# 2Wireless.net
KiCad netlist of a schematic drawn in EAGLE
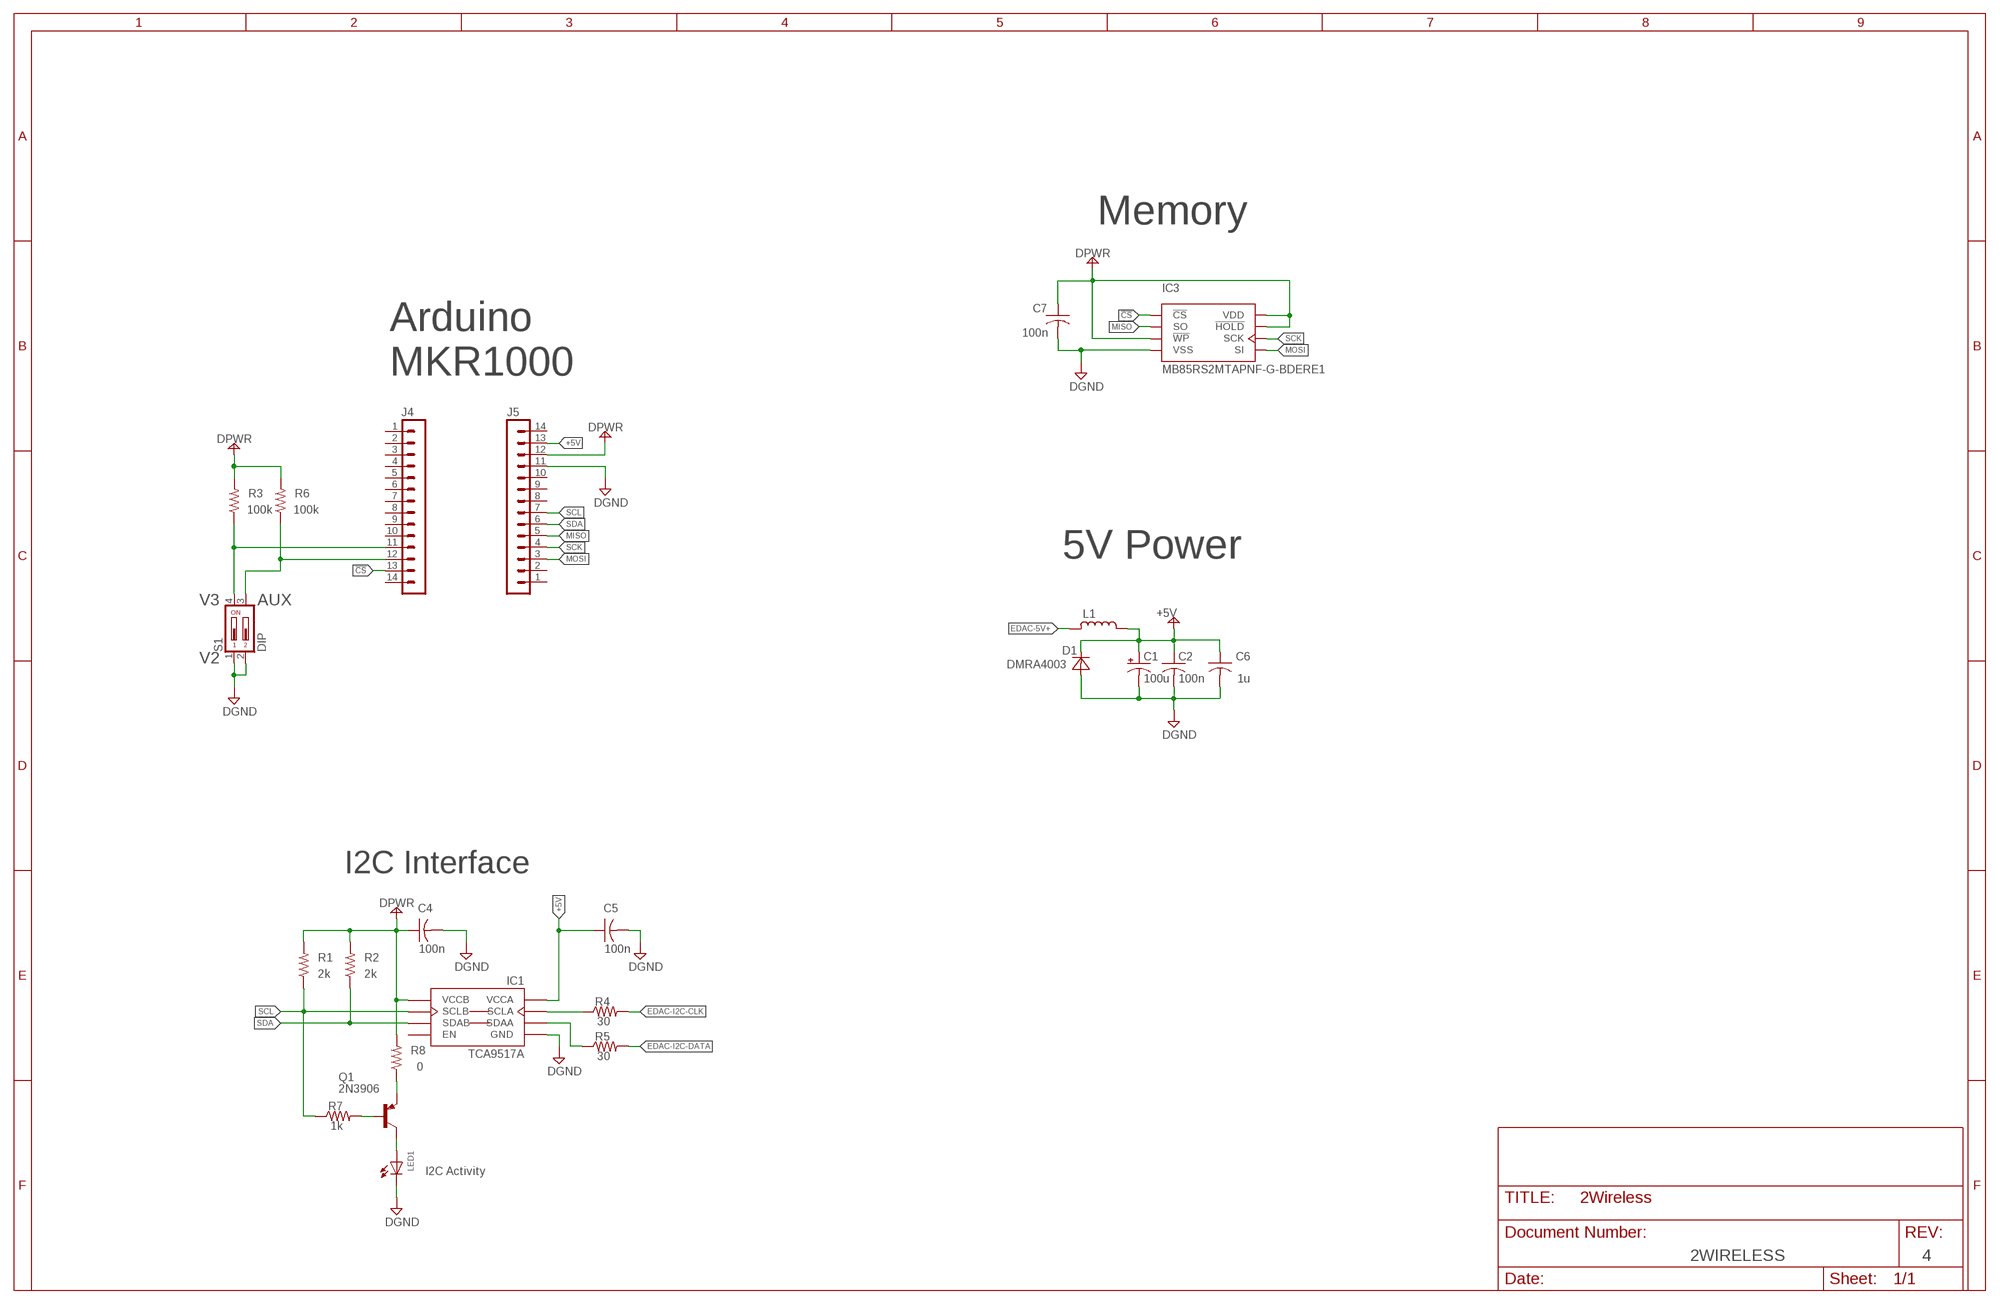
[diagram p0: schematic, sheet 1]

(export (version "E")
  (design (tool "Eeschema 10.0.6"))
  (components
    (comp (ref "C1")
      (value "100u")
      (footprint "eagle-import:PAN-D")
      (fields (field (name "MF") "PANASONIC") (field (name "MPN") "EEE-1CA101WP"))
      (libsource (lib "eagle-import") (part "C-POLPD"))
    )
    (comp (ref "C2")
      (value "100n")
      (footprint "eagle-import:C0603")
      (libsource (lib "eagle-import") (part "CB"))
    )
    (comp (ref "C4")
      (value "100n")
      (footprint "eagle-import:C0603")
      (libsource (lib "eagle-import") (part "CB"))
    )
    (comp (ref "C5")
      (value "100n")
      (footprint "eagle-import:C0603")
      (libsource (lib "eagle-import") (part "CB"))
    )
    (comp (ref "C6")
      (value "1u")
      (footprint "eagle-import:C0603")
      (libsource (lib "eagle-import") (part "CB"))
    )
    (comp (ref "C7")
      (value "100n")
      (footprint "eagle-import:C0603")
      (libsource (lib "eagle-import") (part "CB"))
    )
    (comp (ref "D1")
      (value "DMRA4003")
      (footprint "eagle-import:SMA")
      (fields (field (name "MF") "ON") (field (name "MPN") "MRA4003T3G"))
      (libsource (lib "eagle-import") (part "DMRA4003"))
    )
    (comp (ref "IC1")
      (value "TCA9517A")
      (footprint "eagle-import:MSOP8")
      (fields (field (name "MF") "TI") (field (name "MPN") "TCA9517ADGKR"))
      (libsource (lib "eagle-import") (part "I2C-ISOLATORTCA9517A"))
    )
    (comp (ref "IC3")
      (value "MB85RS2MTAPNF-G-BDERE1")
      (footprint "eagle-import:SO08")
      (fields (field (name "MF") "FUJITSU"))
      (libsource (lib "eagle-import") (part "FRAMSPI"))
    )
    (comp (ref "J4")
      (value "MA14-1")
      (footprint "eagle-import:MA14-1")
      (libsource (lib "eagle-import") (part "MA14-1"))
    )
    (comp (ref "J5")
      (value "MA14-1")
      (footprint "eagle-import:MA14-1")
      (libsource (lib "eagle-import") (part "MA14-1"))
    )
    (comp (ref "L1")
      (value "LB")
      (footprint "eagle-import:0603")
      (fields (field (name "MF") "WURTH") (field (name "MPN") "742792609"))
      (libsource (lib "eagle-import") (part "LB"))
    )
    (comp (ref "LED1")
      (value "LED0805BLUE")
      (footprint "eagle-import:CHIPLED_0805")
      (libsource (lib "eagle-import") (part "LED0805BLUE"))
    )
    (comp (ref "Q1")
      (value "2N3906")
      (footprint "eagle-import:SOT23")
      (fields (field (name "MF") "FAIRCHILD") (field (name "MPN") "MMBT3906"))
      (libsource (lib "eagle-import") (part "PNPMMBT3906"))
    )
    (comp (ref "R1")
      (value "2k")
      (footprint "eagle-import:R0603")
      (libsource (lib "eagle-import") (part "RB"))
    )
    (comp (ref "R2")
      (value "2k")
      (footprint "eagle-import:R0603")
      (libsource (lib "eagle-import") (part "RB"))
    )
    (comp (ref "R3")
      (value "100k")
      (footprint "eagle-import:R0603")
      (libsource (lib "eagle-import") (part "RB"))
    )
    (comp (ref "R4")
      (value "30")
      (footprint "eagle-import:R0603")
      (libsource (lib "eagle-import") (part "RB"))
    )
    (comp (ref "R5")
      (value "30")
      (footprint "eagle-import:R0603")
      (libsource (lib "eagle-import") (part "RB"))
    )
    (comp (ref "R6")
      (value "100k")
      (footprint "eagle-import:R0603")
      (libsource (lib "eagle-import") (part "RB"))
    )
    (comp (ref "R7")
      (value "1k")
      (footprint "eagle-import:R0603")
      (libsource (lib "eagle-import") (part "RB"))
    )
    (comp (ref "R8")
      (value "0")
      (footprint "eagle-import:R0603")
      (libsource (lib "eagle-import") (part "RB"))
    )
    (comp (ref "S1")
      (value "DIP")
      (footprint "eagle-import:CTS-219-02")
      (fields (field (name "MF") "CTS") (field (name "MPN") "219-2MST"))
      (libsource (lib "eagle-import") (part "219-02"))
    )
  )
  (nets
    (net (code "1") (name "+5V") (class "Default")
      (node (ref "C1") (pin "+") (pinfunction "+_+") (pintype "passive"))
      (node (ref "C2") (pin "1") (pinfunction "1_1") (pintype "passive"))
      (node (ref "C5") (pin "1") (pinfunction "1_1") (pintype "passive"))
      (node (ref "C6") (pin "1") (pinfunction "1_1") (pintype "passive"))
      (node (ref "D1") (pin "K") (pinfunction "C_K") (pintype "passive"))
      (node (ref "IC1") (pin "1") (pinfunction "VCCA_1") (pintype "power_in"))
      (node (ref "J5") (pin "13") (pinfunction "13_13") (pintype "passive"))
      (node (ref "L1") (pin "2") (pinfunction "4_2") (pintype "passive"))
    )
    (net (code "2") (name "/~{CS}") (class "Default")
      (node (ref "IC3") (pin "1") (pinfunction "~{CS}_1") (pintype "input"))
      (node (ref "J4") (pin "13") (pinfunction "13_13") (pintype "passive"))
    )
    (net (code "3") (name "DGND") (class "Default")
      (node (ref "C1") (pin "-") (pinfunction "-_-") (pintype "passive"))
      (node (ref "C2") (pin "2") (pinfunction "2_2") (pintype "passive"))
      (node (ref "C4") (pin "2") (pinfunction "2_2") (pintype "passive"))
      (node (ref "C5") (pin "2") (pinfunction "2_2") (pintype "passive"))
      (node (ref "C6") (pin "2") (pinfunction "2_2") (pintype "passive"))
      (node (ref "C7") (pin "2") (pinfunction "2_2") (pintype "passive"))
      (node (ref "D1") (pin "A") (pinfunction "A_A") (pintype "passive"))
      (node (ref "IC1") (pin "4") (pinfunction "GND_4") (pintype "power_in"))
      (node (ref "IC3") (pin "4") (pinfunction "VSS_4") (pintype "power_in"))
      (node (ref "J5") (pin "11") (pinfunction "11_11") (pintype "passive"))
      (node (ref "LED1") (pin "C") (pinfunction "C_C") (pintype "passive"))
      (node (ref "S1") (pin "1") (pinfunction "1_1") (pintype "passive"))
      (node (ref "S1") (pin "2") (pinfunction "2_2") (pintype "passive"))
    )
    (net (code "4") (name "DPWR") (class "Default")
      (node (ref "C4") (pin "1") (pinfunction "1_1") (pintype "passive"))
      (node (ref "C7") (pin "1") (pinfunction "1_1") (pintype "passive"))
      (node (ref "IC1") (pin "8") (pinfunction "VCCB_8") (pintype "power_in"))
      (node (ref "IC3") (pin "3") (pinfunction "~{WP}_3") (pintype "bidirectional"))
      (node (ref "IC3") (pin "7") (pinfunction "~{HOLD}_7") (pintype "bidirectional"))
      (node (ref "IC3") (pin "8") (pinfunction "VDD_8") (pintype "power_in"))
      (node (ref "J5") (pin "12") (pinfunction "12_12") (pintype "passive"))
      (node (ref "R1") (pin "2") (pinfunction "2_2") (pintype "passive"))
      (node (ref "R2") (pin "2") (pinfunction "2_2") (pintype "passive"))
      (node (ref "R3") (pin "2") (pinfunction "2_2") (pintype "passive"))
      (node (ref "R6") (pin "2") (pinfunction "2_2") (pintype "passive"))
      (node (ref "R8") (pin "2") (pinfunction "2_2") (pintype "passive"))
    )
    (net (code "5") (name "EDAC-5V+") (class "Default")
      (node (ref "L1") (pin "1") (pinfunction "1_1") (pintype "passive"))
    )
    (net (code "6") (name "EDAC-I2C-CLK") (class "Default")
      (node (ref "R4") (pin "2") (pinfunction "2_2") (pintype "passive"))
    )
    (net (code "7") (name "EDAC-I2C-DATA") (class "Default")
      (node (ref "R5") (pin "2") (pinfunction "2_2") (pintype "passive"))
    )
    (net (code "8") (name "MISO") (class "Default")
      (node (ref "IC3") (pin "2") (pinfunction "SO_2") (pintype "bidirectional"))
      (node (ref "J5") (pin "5") (pinfunction "5_5") (pintype "passive"))
    )
    (net (code "9") (name "MOSI") (class "Default")
      (node (ref "IC3") (pin "5") (pinfunction "SI_5") (pintype "bidirectional"))
      (node (ref "J5") (pin "3") (pinfunction "3_3") (pintype "passive"))
    )
    (net (code "10") (name "Net-(IC1-SCLA)") (class "Default")
      (node (ref "IC1") (pin "2") (pinfunction "SCLA_2") (pintype "bidirectional"))
      (node (ref "R4") (pin "1") (pinfunction "1_1") (pintype "passive"))
    )
    (net (code "11") (name "Net-(IC1-SDAA)") (class "Default")
      (node (ref "IC1") (pin "3") (pinfunction "SDAA_3") (pintype "bidirectional"))
      (node (ref "R5") (pin "1") (pinfunction "1_1") (pintype "passive"))
    )
    (net (code "12") (name "Net-(J4-Pad11)") (class "Default")
      (node (ref "J4") (pin "11") (pinfunction "11_11") (pintype "passive"))
      (node (ref "R3") (pin "1") (pinfunction "1_1") (pintype "passive"))
      (node (ref "S1") (pin "4") (pinfunction "4_4") (pintype "passive"))
    )
    (net (code "13") (name "Net-(J4-Pad12)") (class "Default")
      (node (ref "J4") (pin "12") (pinfunction "12_12") (pintype "passive"))
      (node (ref "R6") (pin "1") (pinfunction "1_1") (pintype "passive"))
      (node (ref "S1") (pin "3") (pinfunction "3_3") (pintype "passive"))
    )
    (net (code "14") (name "Net-(Q1-B)") (class "Default")
      (node (ref "Q1") (pin "1") (pinfunction "B_1") (pintype "passive"))
      (node (ref "R7") (pin "2") (pinfunction "2_2") (pintype "passive"))
    )
    (net (code "15") (name "Net-(Q1-C)") (class "Default")
      (node (ref "LED1") (pin "A") (pinfunction "A_A") (pintype "passive"))
      (node (ref "Q1") (pin "2") (pinfunction "C_2") (pintype "passive"))
    )
    (net (code "16") (name "Net-(Q1-E)") (class "Default")
      (node (ref "Q1") (pin "3") (pinfunction "E_3") (pintype "passive"))
      (node (ref "R8") (pin "1") (pinfunction "1_1") (pintype "passive"))
    )
    (net (code "17") (name "SCK") (class "Default")
      (node (ref "IC3") (pin "6") (pinfunction "SCK_6") (pintype "bidirectional"))
      (node (ref "J5") (pin "4") (pinfunction "4_4") (pintype "passive"))
    )
    (net (code "18") (name "SCL") (class "Default")
      (node (ref "IC1") (pin "7") (pinfunction "SCLB_7") (pintype "bidirectional"))
      (node (ref "J5") (pin "7") (pinfunction "7_7") (pintype "passive"))
      (node (ref "R1") (pin "1") (pinfunction "1_1") (pintype "passive"))
      (node (ref "R7") (pin "1") (pinfunction "1_1") (pintype "passive"))
    )
    (net (code "19") (name "SDA") (class "Default")
      (node (ref "IC1") (pin "6") (pinfunction "SDAB_6") (pintype "bidirectional"))
      (node (ref "J5") (pin "6") (pinfunction "6_6") (pintype "passive"))
      (node (ref "R2") (pin "1") (pinfunction "1_1") (pintype "passive"))
    )
    (net (code "20") (name "unconnected-(IC1-EN-Pad5)") (class "Default")
      (node (ref "IC1") (pin "5") (pinfunction "EN_5") (pintype "input"))
    )
    (net (code "21") (name "unconnected-(J4-Pad1)") (class "Default")
      (node (ref "J4") (pin "1") (pinfunction "1_1") (pintype "passive"))
    )
    (net (code "22") (name "unconnected-(J4-Pad2)") (class "Default")
      (node (ref "J4") (pin "2") (pinfunction "2_2") (pintype "passive"))
    )
    (net (code "23") (name "unconnected-(J4-Pad3)") (class "Default")
      (node (ref "J4") (pin "3") (pinfunction "3_3") (pintype "passive"))
    )
    (net (code "24") (name "unconnected-(J4-Pad4)") (class "Default")
      (node (ref "J4") (pin "4") (pinfunction "4_4") (pintype "passive"))
    )
    (net (code "25") (name "unconnected-(J4-Pad5)") (class "Default")
      (node (ref "J4") (pin "5") (pinfunction "5_5") (pintype "passive"))
    )
    (net (code "26") (name "unconnected-(J4-Pad6)") (class "Default")
      (node (ref "J4") (pin "6") (pinfunction "6_6") (pintype "passive"))
    )
    (net (code "27") (name "unconnected-(J4-Pad7)") (class "Default")
      (node (ref "J4") (pin "7") (pinfunction "7_7") (pintype "passive"))
    )
    (net (code "28") (name "unconnected-(J4-Pad8)") (class "Default")
      (node (ref "J4") (pin "8") (pinfunction "8_8") (pintype "passive"))
    )
    (net (code "29") (name "unconnected-(J4-Pad9)") (class "Default")
      (node (ref "J4") (pin "9") (pinfunction "9_9") (pintype "passive"))
    )
    (net (code "30") (name "unconnected-(J4-Pad10)") (class "Default")
      (node (ref "J4") (pin "10") (pinfunction "10_10") (pintype "passive"))
    )
    (net (code "31") (name "unconnected-(J4-Pad14)") (class "Default")
      (node (ref "J4") (pin "14") (pinfunction "14_14") (pintype "passive"))
    )
    (net (code "32") (name "unconnected-(J5-Pad1)") (class "Default")
      (node (ref "J5") (pin "1") (pinfunction "1_1") (pintype "passive"))
    )
    (net (code "33") (name "unconnected-(J5-Pad2)") (class "Default")
      (node (ref "J5") (pin "2") (pinfunction "2_2") (pintype "passive"))
    )
    (net (code "34") (name "unconnected-(J5-Pad8)") (class "Default")
      (node (ref "J5") (pin "8") (pinfunction "8_8") (pintype "passive"))
    )
    (net (code "35") (name "unconnected-(J5-Pad9)") (class "Default")
      (node (ref "J5") (pin "9") (pinfunction "9_9") (pintype "passive"))
    )
    (net (code "36") (name "unconnected-(J5-Pad10)") (class "Default")
      (node (ref "J5") (pin "10") (pinfunction "10_10") (pintype "passive"))
    )
    (net (code "37") (name "unconnected-(J5-Pad14)") (class "Default")
      (node (ref "J5") (pin "14") (pinfunction "14_14") (pintype "passive"))
    )
  )
)
